# charger.net
KiCad netlist of a schematic drawn in EAGLE
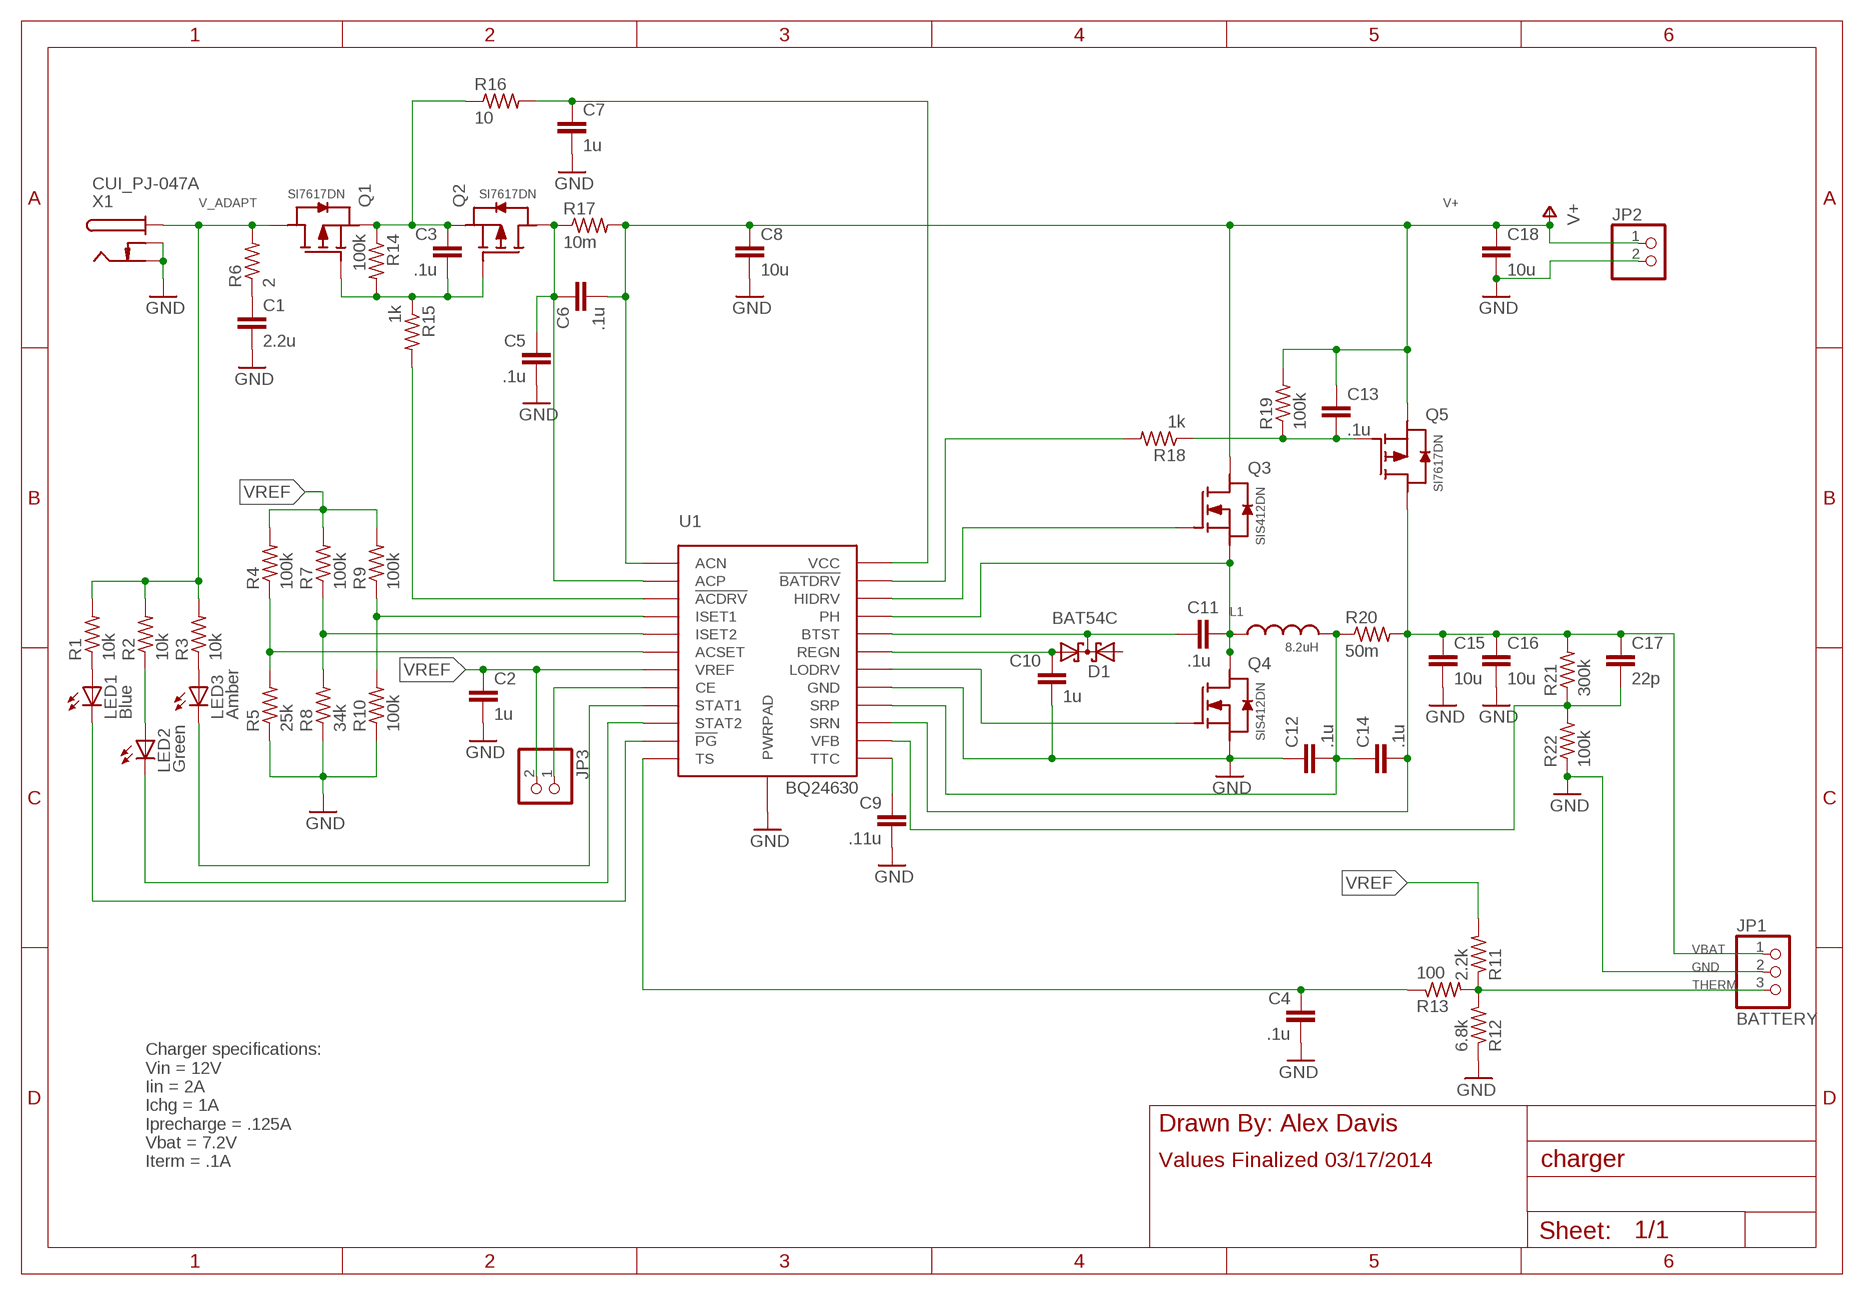
[diagram p0: schematic, sheet 1]

(export (version "E")
  (design (tool "Eeschema 10.0.6"))
  (components
    (comp (ref "C1")
      (value "2.2u")
      (footprint "eagle-import:C0603")
      (libsource (lib "eagle-import") (part "C-EUC0603"))
    )
    (comp (ref "C2")
      (value "1u")
      (footprint "eagle-import:C0603")
      (libsource (lib "eagle-import") (part "C-EUC0603"))
    )
    (comp (ref "C3")
      (value ".1u")
      (footprint "eagle-import:C0603")
      (libsource (lib "eagle-import") (part "C-EUC0603"))
    )
    (comp (ref "C4")
      (value ".1u")
      (footprint "eagle-import:C0603")
      (libsource (lib "eagle-import") (part "C-EUC0603"))
    )
    (comp (ref "C5")
      (value ".1u")
      (footprint "eagle-import:C0603")
      (libsource (lib "eagle-import") (part "C-EUC0603"))
    )
    (comp (ref "C6")
      (value ".1u")
      (footprint "eagle-import:C0603")
      (libsource (lib "eagle-import") (part "C-EUC0603"))
    )
    (comp (ref "C7")
      (value "1u")
      (footprint "eagle-import:C0603")
      (libsource (lib "eagle-import") (part "C-EUC0603"))
    )
    (comp (ref "C8")
      (value "10u")
      (footprint "eagle-import:C0805")
      (libsource (lib "eagle-import") (part "C-EUC0805"))
    )
    (comp (ref "C9")
      (value ".11u")
      (footprint "eagle-import:C0603")
      (libsource (lib "eagle-import") (part "C-EUC0603"))
    )
    (comp (ref "C10")
      (value "1u")
      (footprint "eagle-import:C0603")
      (libsource (lib "eagle-import") (part "C-EUC0603"))
    )
    (comp (ref "C11")
      (value ".1u")
      (footprint "eagle-import:C0603")
      (libsource (lib "eagle-import") (part "C-EUC0603"))
    )
    (comp (ref "C12")
      (value ".1u")
      (footprint "eagle-import:C0603")
      (libsource (lib "eagle-import") (part "C-EUC0603"))
    )
    (comp (ref "C13")
      (value ".1u")
      (footprint "eagle-import:C0603")
      (libsource (lib "eagle-import") (part "C-EUC0603"))
    )
    (comp (ref "C14")
      (value ".1u")
      (footprint "eagle-import:C0603")
      (libsource (lib "eagle-import") (part "C-EUC0603"))
    )
    (comp (ref "C15")
      (value "10u")
      (footprint "eagle-import:C0805")
      (libsource (lib "eagle-import") (part "C-EUC0805"))
    )
    (comp (ref "C16")
      (value "10u")
      (footprint "eagle-import:C0805")
      (libsource (lib "eagle-import") (part "C-EUC0805"))
    )
    (comp (ref "C17")
      (value "22p")
      (footprint "eagle-import:C0603")
      (libsource (lib "eagle-import") (part "C-EUC0603"))
    )
    (comp (ref "C18")
      (value "10u")
      (footprint "eagle-import:C0805")
      (libsource (lib "eagle-import") (part "C-EUC0805"))
    )
    (comp (ref "D1")
      (value "BAT54C")
      (footprint "eagle-import:SOT23")
      (libsource (lib "eagle-import") (part "BAT54C"))
    )
    (comp (ref "JP1")
      (value "BATTERY")
      (footprint "eagle-import:1X03")
      (libsource (lib "eagle-import") (part "PINHD-1X3"))
    )
    (comp (ref "JP2")
      (value "PINHD-1X2")
      (footprint "eagle-import:1X02")
      (libsource (lib "eagle-import") (part "PINHD-1X2"))
    )
    (comp (ref "JP3")
      (value "PINHD-1X2")
      (footprint "eagle-import:1X02")
      (libsource (lib "eagle-import") (part "PINHD-1X2"))
    )
    (comp (ref "L1")
      (value "8.2uH")
      (footprint "eagle-import:IHLP-2525CZ")
      (libsource (lib "eagle-import") (part "IHLP-2525CZ-01"))
    )
    (comp (ref "LED1")
      (value "Blue")
      (footprint "eagle-import:CHIPLED_0805")
      (libsource (lib "eagle-import") (part "LEDCHIPLED_0805"))
    )
    (comp (ref "LED2")
      (value "Green")
      (footprint "eagle-import:CHIPLED_0805")
      (libsource (lib "eagle-import") (part "LEDCHIPLED_0805"))
    )
    (comp (ref "LED3")
      (value "Amber")
      (footprint "eagle-import:CHIPLED_0805")
      (libsource (lib "eagle-import") (part "LEDCHIPLED_0805"))
    )
    (comp (ref "Q1")
      (value "SI7617DN")
      (footprint "eagle-import:POWERPAK1212-8")
      (libsource (lib "eagle-import") (part "SI7617DN"))
    )
    (comp (ref "Q2")
      (value "SI7617DN")
      (footprint "eagle-import:POWERPAK1212-8")
      (libsource (lib "eagle-import") (part "SI7617DN"))
    )
    (comp (ref "Q3")
      (value "SIS412DN")
      (footprint "eagle-import:POWERPAK1212-8")
      (libsource (lib "eagle-import") (part "SIS412DN"))
    )
    (comp (ref "Q4")
      (value "SIS412DN")
      (footprint "eagle-import:POWERPAK1212-8")
      (libsource (lib "eagle-import") (part "SIS412DN"))
    )
    (comp (ref "Q5")
      (value "SI7617DN")
      (footprint "eagle-import:POWERPAK1212-8")
      (libsource (lib "eagle-import") (part "SI7617DN"))
    )
    (comp (ref "R1")
      (value "10k")
      (footprint "eagle-import:R0603")
      (libsource (lib "eagle-import") (part "R-US_R0603"))
    )
    (comp (ref "R2")
      (value "10k")
      (footprint "eagle-import:R0603")
      (libsource (lib "eagle-import") (part "R-US_R0603"))
    )
    (comp (ref "R3")
      (value "10k")
      (footprint "eagle-import:R0603")
      (libsource (lib "eagle-import") (part "R-US_R0603"))
    )
    (comp (ref "R4")
      (value "100k")
      (footprint "eagle-import:R0603")
      (libsource (lib "eagle-import") (part "R-US_R0603"))
    )
    (comp (ref "R5")
      (value "25k")
      (footprint "eagle-import:R0603")
      (libsource (lib "eagle-import") (part "R-US_R0603"))
    )
    (comp (ref "R6")
      (value "2")
      (footprint "eagle-import:R2512")
      (libsource (lib "eagle-import") (part "R-US_R2512"))
    )
    (comp (ref "R7")
      (value "100k")
      (footprint "eagle-import:R0603")
      (libsource (lib "eagle-import") (part "R-US_R0603"))
    )
    (comp (ref "R8")
      (value "34k")
      (footprint "eagle-import:R0603")
      (libsource (lib "eagle-import") (part "R-US_R0603"))
    )
    (comp (ref "R9")
      (value "100k")
      (footprint "eagle-import:R0603")
      (libsource (lib "eagle-import") (part "R-US_R0603"))
    )
    (comp (ref "R10")
      (value "100k")
      (footprint "eagle-import:R0603")
      (libsource (lib "eagle-import") (part "R-US_R0603"))
    )
    (comp (ref "R11")
      (value "2.2k")
      (footprint "eagle-import:R0603")
      (libsource (lib "eagle-import") (part "R-US_R0603"))
    )
    (comp (ref "R12")
      (value "6.8k")
      (footprint "eagle-import:R0603")
      (libsource (lib "eagle-import") (part "R-US_R0603"))
    )
    (comp (ref "R13")
      (value "100")
      (footprint "eagle-import:R0603")
      (libsource (lib "eagle-import") (part "R-US_R0603"))
    )
    (comp (ref "R14")
      (value "100k")
      (footprint "eagle-import:R0603")
      (libsource (lib "eagle-import") (part "R-US_R0603"))
    )
    (comp (ref "R15")
      (value "1k")
      (footprint "eagle-import:R0603")
      (libsource (lib "eagle-import") (part "R-US_R0603"))
    )
    (comp (ref "R16")
      (value "10")
      (footprint "eagle-import:R1206")
      (libsource (lib "eagle-import") (part "R-US_R1206"))
    )
    (comp (ref "R17")
      (value "10m")
      (footprint "eagle-import:R2010")
      (libsource (lib "eagle-import") (part "R-US_R2010"))
    )
    (comp (ref "R18")
      (value "1k")
      (footprint "eagle-import:R0603")
      (libsource (lib "eagle-import") (part "R-US_R0603"))
    )
    (comp (ref "R19")
      (value "100k")
      (footprint "eagle-import:R0603")
      (libsource (lib "eagle-import") (part "R-US_R0603"))
    )
    (comp (ref "R20")
      (value "50m")
      (footprint "eagle-import:R2010")
      (libsource (lib "eagle-import") (part "R-US_R2010"))
    )
    (comp (ref "R21")
      (value "300k")
      (footprint "eagle-import:R0603")
      (libsource (lib "eagle-import") (part "R-US_R0603"))
    )
    (comp (ref "R22")
      (value "100k")
      (footprint "eagle-import:R0603")
      (libsource (lib "eagle-import") (part "R-US_R0603"))
    )
    (comp (ref "U1")
      (value "BQ24630")
      (footprint "eagle-import:PVQFN-24")
      (libsource (lib "eagle-import") (part "BQ24630"))
    )
    (comp (ref "X1")
      (value "CUI_PJ-047A")
      (footprint "eagle-import:PJ-047A")
      (libsource (lib "eagle-import") (part "CON-PWR"))
    )
  )
  (nets
    (net (code "1") (name "/THERM") (class "Default")
      (node (ref "JP1") (pin "3") (pinfunction "3_3") (pintype "passive"))
      (node (ref "R11") (pin "1") (pinfunction "1_1") (pintype "passive"))
      (node (ref "R12") (pin "2") (pinfunction "2_2") (pintype "passive"))
      (node (ref "R13") (pin "2") (pinfunction "2_2") (pintype "passive"))
    )
    (net (code "2") (name "/VBAT") (class "Default")
      (node (ref "C14") (pin "2") (pinfunction "2_2") (pintype "passive"))
      (node (ref "C15") (pin "1") (pinfunction "1_1") (pintype "passive"))
      (node (ref "C16") (pin "1") (pinfunction "1_1") (pintype "passive"))
      (node (ref "C17") (pin "1") (pinfunction "1_1") (pintype "passive"))
      (node (ref "JP1") (pin "1") (pinfunction "1_1") (pintype "passive"))
      (node (ref "Q5") (pin "P$5") (pinfunction "D_P$5") (pintype "bidirectional"))
      (node (ref "Q5") (pin "P$6") (pinfunction "D_P$6") (pintype "bidirectional"))
      (node (ref "Q5") (pin "P$7") (pinfunction "D_P$7") (pintype "bidirectional"))
      (node (ref "Q5") (pin "P$8") (pinfunction "D_P$8") (pintype "bidirectional"))
      (node (ref "Q5") (pin "P$9") (pinfunction "D_P$9") (pintype "bidirectional"))
      (node (ref "R20") (pin "2") (pinfunction "2_2") (pintype "passive"))
      (node (ref "R21") (pin "2") (pinfunction "2_2") (pintype "passive"))
      (node (ref "U1") (pin "P$13") (pinfunction "SRN_P$13") (pintype "bidirectional"))
    )
    (net (code "3") (name "/V_ADAPT") (class "Default")
      (node (ref "Q1") (pin "P$5") (pinfunction "D_P$5") (pintype "bidirectional"))
      (node (ref "Q1") (pin "P$6") (pinfunction "D_P$6") (pintype "bidirectional"))
      (node (ref "Q1") (pin "P$7") (pinfunction "D_P$7") (pintype "bidirectional"))
      (node (ref "Q1") (pin "P$8") (pinfunction "D_P$8") (pintype "bidirectional"))
      (node (ref "Q1") (pin "P$9") (pinfunction "D_P$9") (pintype "bidirectional"))
      (node (ref "R1") (pin "2") (pinfunction "2_2") (pintype "passive"))
      (node (ref "R2") (pin "2") (pinfunction "2_2") (pintype "passive"))
      (node (ref "R3") (pin "2") (pinfunction "2_2") (pintype "passive"))
      (node (ref "R6") (pin "2") (pinfunction "2_2") (pintype "passive"))
      (node (ref "X1") (pin "1") (pinfunction "1_1") (pintype "bidirectional"))
    )
    (net (code "4") (name "GND") (class "Default")
      (node (ref "C1") (pin "2") (pinfunction "2_2") (pintype "passive"))
      (node (ref "C10") (pin "2") (pinfunction "2_2") (pintype "passive"))
      (node (ref "C12") (pin "1") (pinfunction "1_1") (pintype "passive"))
      (node (ref "C15") (pin "2") (pinfunction "2_2") (pintype "passive"))
      (node (ref "C16") (pin "2") (pinfunction "2_2") (pintype "passive"))
      (node (ref "C18") (pin "2") (pinfunction "2_2") (pintype "passive"))
      (node (ref "C2") (pin "2") (pinfunction "2_2") (pintype "passive"))
      (node (ref "C4") (pin "2") (pinfunction "2_2") (pintype "passive"))
      (node (ref "C5") (pin "2") (pinfunction "2_2") (pintype "passive"))
      (node (ref "C7") (pin "2") (pinfunction "2_2") (pintype "passive"))
      (node (ref "C8") (pin "2") (pinfunction "2_2") (pintype "passive"))
      (node (ref "C9") (pin "2") (pinfunction "2_2") (pintype "passive"))
      (node (ref "JP1") (pin "2") (pinfunction "2_2") (pintype "passive"))
      (node (ref "JP2") (pin "2") (pinfunction "2_2") (pintype "passive"))
      (node (ref "Q4") (pin "P$1") (pinfunction "S_P$1") (pintype "bidirectional"))
      (node (ref "Q4") (pin "P$2") (pinfunction "S_P$2") (pintype "bidirectional"))
      (node (ref "Q4") (pin "P$3") (pinfunction "S_P$3") (pintype "bidirectional"))
      (node (ref "R10") (pin "1") (pinfunction "1_1") (pintype "passive"))
      (node (ref "R12") (pin "1") (pinfunction "1_1") (pintype "passive"))
      (node (ref "R22") (pin "1") (pinfunction "1_1") (pintype "passive"))
      (node (ref "R5") (pin "1") (pinfunction "1_1") (pintype "passive"))
      (node (ref "R8") (pin "1") (pinfunction "1_1") (pintype "passive"))
      (node (ref "U1") (pin "P$17") (pinfunction "GND_P$17") (pintype "bidirectional"))
      (node (ref "U1") (pin "P$25") (pinfunction "PWRPAD_P$25") (pintype "bidirectional"))
      (node (ref "X1") (pin "2") (pinfunction "2_2") (pintype "bidirectional"))
      (node (ref "X1") (pin "3") (pinfunction "3_3") (pintype "bidirectional"))
    )
    (net (code "5") (name "Net-(C1-Pad1)") (class "Default")
      (node (ref "C1") (pin "1") (pinfunction "1_1") (pintype "passive"))
      (node (ref "R6") (pin "1") (pinfunction "1_1") (pintype "passive"))
    )
    (net (code "6") (name "Net-(C3-Pad1)") (class "Default")
      (node (ref "C3") (pin "1") (pinfunction "1_1") (pintype "passive"))
      (node (ref "Q1") (pin "P$1") (pinfunction "S_P$1") (pintype "bidirectional"))
      (node (ref "Q1") (pin "P$2") (pinfunction "S_P$2") (pintype "bidirectional"))
      (node (ref "Q1") (pin "P$3") (pinfunction "S_P$3") (pintype "bidirectional"))
      (node (ref "Q2") (pin "P$1") (pinfunction "S_P$1") (pintype "bidirectional"))
      (node (ref "Q2") (pin "P$2") (pinfunction "S_P$2") (pintype "bidirectional"))
      (node (ref "Q2") (pin "P$3") (pinfunction "S_P$3") (pintype "bidirectional"))
      (node (ref "R14") (pin "1") (pinfunction "1_1") (pintype "passive"))
      (node (ref "R16") (pin "1") (pinfunction "1_1") (pintype "passive"))
    )
    (net (code "7") (name "Net-(D1-A2)") (class "Default")
      (node (ref "C10") (pin "1") (pinfunction "1_1") (pintype "passive"))
      (node (ref "D1") (pin "2") (pinfunction "A2_2") (pintype "passive"))
      (node (ref "U1") (pin "P$18") (pinfunction "REGN_P$18") (pintype "bidirectional"))
    )
    (net (code "8") (name "Net-(D1-CC)") (class "Default")
      (node (ref "C11") (pin "1") (pinfunction "1_1") (pintype "passive"))
      (node (ref "D1") (pin "3") (pinfunction "CC_3") (pintype "passive"))
      (node (ref "U1") (pin "P$22") (pinfunction "BTST_P$22") (pintype "bidirectional"))
    )
    (net (code "9") (name "Net-(LED1-PadA)") (class "Default")
      (node (ref "LED1") (pin "A") (pinfunction "A_A") (pintype "passive"))
      (node (ref "R1") (pin "1") (pinfunction "1_1") (pintype "passive"))
    )
    (net (code "10") (name "Net-(LED2-PadA)") (class "Default")
      (node (ref "LED2") (pin "A") (pinfunction "A_A") (pintype "passive"))
      (node (ref "R2") (pin "1") (pinfunction "1_1") (pintype "passive"))
    )
    (net (code "11") (name "Net-(LED3-PadA)") (class "Default")
      (node (ref "LED3") (pin "A") (pinfunction "A_A") (pintype "passive"))
      (node (ref "R3") (pin "1") (pinfunction "1_1") (pintype "passive"))
    )
    (net (code "12") (name "Net-(Q1-G)") (class "Default")
      (node (ref "C3") (pin "2") (pinfunction "2_2") (pintype "passive"))
      (node (ref "Q1") (pin "P$4") (pinfunction "G_P$4") (pintype "bidirectional"))
      (node (ref "Q2") (pin "P$4") (pinfunction "G_P$4") (pintype "bidirectional"))
      (node (ref "R14") (pin "2") (pinfunction "2_2") (pintype "passive"))
      (node (ref "R15") (pin "1") (pinfunction "1_1") (pintype "passive"))
    )
    (net (code "13") (name "Net-(Q3-G)") (class "Default")
      (node (ref "Q3") (pin "P$4") (pinfunction "G_P$4") (pintype "bidirectional"))
      (node (ref "U1") (pin "P$21") (pinfunction "HIDRV_P$21") (pintype "bidirectional"))
    )
    (net (code "14") (name "Net-(Q4-G)") (class "Default")
      (node (ref "Q4") (pin "P$4") (pinfunction "G_P$4") (pintype "bidirectional"))
      (node (ref "U1") (pin "P$19") (pinfunction "LODRV_P$19") (pintype "bidirectional"))
    )
    (net (code "15") (name "Net-(Q5-G)") (class "Default")
      (node (ref "C13") (pin "2") (pinfunction "2_2") (pintype "passive"))
      (node (ref "Q5") (pin "P$4") (pinfunction "G_P$4") (pintype "bidirectional"))
      (node (ref "R18") (pin "1") (pinfunction "1_1") (pintype "passive"))
      (node (ref "R19") (pin "1") (pinfunction "1_1") (pintype "passive"))
    )
    (net (code "16") (name "Net-(U1-ACP)") (class "Default")
      (node (ref "C5") (pin "1") (pinfunction "1_1") (pintype "passive"))
      (node (ref "C6") (pin "1") (pinfunction "1_1") (pintype "passive"))
      (node (ref "Q2") (pin "P$5") (pinfunction "D_P$5") (pintype "bidirectional"))
      (node (ref "Q2") (pin "P$6") (pinfunction "D_P$6") (pintype "bidirectional"))
      (node (ref "Q2") (pin "P$7") (pinfunction "D_P$7") (pintype "bidirectional"))
      (node (ref "Q2") (pin "P$8") (pinfunction "D_P$8") (pintype "bidirectional"))
      (node (ref "Q2") (pin "P$9") (pinfunction "D_P$9") (pintype "bidirectional"))
      (node (ref "R17") (pin "1") (pinfunction "1_1") (pintype "passive"))
      (node (ref "U1") (pin "P$2") (pinfunction "ACP_P$2") (pintype "bidirectional"))
    )
    (net (code "17") (name "Net-(U1-ACSET)") (class "Default")
      (node (ref "R4") (pin "1") (pinfunction "1_1") (pintype "passive"))
      (node (ref "R5") (pin "2") (pinfunction "2_2") (pintype "passive"))
      (node (ref "U1") (pin "P$16") (pinfunction "ACSET_P$16") (pintype "bidirectional"))
    )
    (net (code "18") (name "Net-(U1-CE)") (class "Default")
      (node (ref "JP3") (pin "1") (pinfunction "1_1") (pintype "passive"))
      (node (ref "U1") (pin "P$4") (pinfunction "CE_P$4") (pintype "bidirectional"))
    )
    (net (code "19") (name "Net-(U1-ISET1)") (class "Default")
      (node (ref "R10") (pin "2") (pinfunction "2_2") (pintype "passive"))
      (node (ref "R9") (pin "1") (pinfunction "1_1") (pintype "passive"))
      (node (ref "U1") (pin "P$11") (pinfunction "ISET1_P$11") (pintype "bidirectional"))
    )
    (net (code "20") (name "Net-(U1-ISET2)") (class "Default")
      (node (ref "R7") (pin "1") (pinfunction "1_1") (pintype "passive"))
      (node (ref "R8") (pin "2") (pinfunction "2_2") (pintype "passive"))
      (node (ref "U1") (pin "P$15") (pinfunction "ISET2_P$15") (pintype "bidirectional"))
    )
    (net (code "21") (name "Net-(U1-PH)") (class "Default")
      (node (ref "C11") (pin "2") (pinfunction "2_2") (pintype "passive"))
      (node (ref "L1") (pin "P$1") (pinfunction "P$1_P$1") (pintype "bidirectional"))
      (node (ref "Q3") (pin "P$1") (pinfunction "S_P$1") (pintype "bidirectional"))
      (node (ref "Q3") (pin "P$2") (pinfunction "S_P$2") (pintype "bidirectional"))
      (node (ref "Q3") (pin "P$3") (pinfunction "S_P$3") (pintype "bidirectional"))
      (node (ref "Q4") (pin "P$5") (pinfunction "D_P$5") (pintype "bidirectional"))
      (node (ref "Q4") (pin "P$6") (pinfunction "D_P$6") (pintype "bidirectional"))
      (node (ref "Q4") (pin "P$7") (pinfunction "D_P$7") (pintype "bidirectional"))
      (node (ref "Q4") (pin "P$8") (pinfunction "D_P$8") (pintype "bidirectional"))
      (node (ref "Q4") (pin "P$9") (pinfunction "D_P$9") (pintype "bidirectional"))
      (node (ref "U1") (pin "P$20") (pinfunction "PH_P$20") (pintype "bidirectional"))
    )
    (net (code "22") (name "Net-(U1-SRP)") (class "Default")
      (node (ref "C12") (pin "2") (pinfunction "2_2") (pintype "passive"))
      (node (ref "C14") (pin "1") (pinfunction "1_1") (pintype "passive"))
      (node (ref "L1") (pin "P$2") (pinfunction "P$2_P$2") (pintype "bidirectional"))
      (node (ref "R20") (pin "1") (pinfunction "1_1") (pintype "passive"))
      (node (ref "U1") (pin "P$14") (pinfunction "SRP_P$14") (pintype "bidirectional"))
    )
    (net (code "23") (name "Net-(U1-STAT1)") (class "Default")
      (node (ref "LED3") (pin "C") (pinfunction "C_C") (pintype "passive"))
      (node (ref "U1") (pin "P$5") (pinfunction "STAT1_P$5") (pintype "bidirectional"))
    )
    (net (code "24") (name "Net-(U1-STAT2)") (class "Default")
      (node (ref "LED2") (pin "C") (pinfunction "C_C") (pintype "passive"))
      (node (ref "U1") (pin "P$9") (pinfunction "STAT2_P$9") (pintype "bidirectional"))
    )
    (net (code "25") (name "Net-(U1-TS)") (class "Default")
      (node (ref "C4") (pin "1") (pinfunction "1_1") (pintype "passive"))
      (node (ref "R13") (pin "1") (pinfunction "1_1") (pintype "passive"))
      (node (ref "U1") (pin "P$6") (pinfunction "TS_P$6") (pintype "bidirectional"))
    )
    (net (code "26") (name "Net-(U1-TTC)") (class "Default")
      (node (ref "C9") (pin "1") (pinfunction "1_1") (pintype "passive"))
      (node (ref "U1") (pin "P$7") (pinfunction "TTC_P$7") (pintype "bidirectional"))
    )
    (net (code "27") (name "Net-(U1-VCC)") (class "Default")
      (node (ref "C7") (pin "1") (pinfunction "1_1") (pintype "passive"))
      (node (ref "R16") (pin "2") (pinfunction "2_2") (pintype "passive"))
      (node (ref "U1") (pin "P$24") (pinfunction "VCC_P$24") (pintype "bidirectional"))
    )
    (net (code "28") (name "Net-(U1-VFB)") (class "Default")
      (node (ref "C17") (pin "2") (pinfunction "2_2") (pintype "passive"))
      (node (ref "R21") (pin "1") (pinfunction "1_1") (pintype "passive"))
      (node (ref "R22") (pin "2") (pinfunction "2_2") (pintype "passive"))
      (node (ref "U1") (pin "P$12") (pinfunction "VFB_P$12") (pintype "bidirectional"))
    )
    (net (code "29") (name "Net-(U1-~{ACDRV})") (class "Default")
      (node (ref "R15") (pin "2") (pinfunction "2_2") (pintype "passive"))
      (node (ref "U1") (pin "P$3") (pinfunction "~{ACDRV}_P$3") (pintype "bidirectional"))
    )
    (net (code "30") (name "Net-(U1-~{BATDRV})") (class "Default")
      (node (ref "R18") (pin "2") (pinfunction "2_2") (pintype "passive"))
      (node (ref "U1") (pin "P$23") (pinfunction "~{BATDRV}_P$23") (pintype "bidirectional"))
    )
    (net (code "31") (name "Net-(U1-~{PG})") (class "Default")
      (node (ref "LED1") (pin "C") (pinfunction "C_C") (pintype "passive"))
      (node (ref "U1") (pin "P$8") (pinfunction "~{PG}_P$8") (pintype "bidirectional"))
    )
    (net (code "32") (name "V+") (class "Default")
      (node (ref "C13") (pin "1") (pinfunction "1_1") (pintype "passive"))
      (node (ref "C18") (pin "1") (pinfunction "1_1") (pintype "passive"))
      (node (ref "C6") (pin "2") (pinfunction "2_2") (pintype "passive"))
      (node (ref "C8") (pin "1") (pinfunction "1_1") (pintype "passive"))
      (node (ref "JP2") (pin "1") (pinfunction "1_1") (pintype "passive"))
      (node (ref "Q3") (pin "P$5") (pinfunction "D_P$5") (pintype "bidirectional"))
      (node (ref "Q3") (pin "P$6") (pinfunction "D_P$6") (pintype "bidirectional"))
      (node (ref "Q3") (pin "P$7") (pinfunction "D_P$7") (pintype "bidirectional"))
      (node (ref "Q3") (pin "P$8") (pinfunction "D_P$8") (pintype "bidirectional"))
      (node (ref "Q3") (pin "P$9") (pinfunction "D_P$9") (pintype "bidirectional"))
      (node (ref "Q5") (pin "P$1") (pinfunction "S_P$1") (pintype "bidirectional"))
      (node (ref "Q5") (pin "P$2") (pinfunction "S_P$2") (pintype "bidirectional"))
      (node (ref "Q5") (pin "P$3") (pinfunction "S_P$3") (pintype "bidirectional"))
      (node (ref "R17") (pin "2") (pinfunction "2_2") (pintype "passive"))
      (node (ref "R19") (pin "2") (pinfunction "2_2") (pintype "passive"))
      (node (ref "U1") (pin "P$1") (pinfunction "ACN_P$1") (pintype "bidirectional"))
    )
    (net (code "33") (name "VREF") (class "Default")
      (node (ref "C2") (pin "1") (pinfunction "1_1") (pintype "passive"))
      (node (ref "JP3") (pin "2") (pinfunction "2_2") (pintype "passive"))
      (node (ref "R11") (pin "2") (pinfunction "2_2") (pintype "passive"))
      (node (ref "R4") (pin "2") (pinfunction "2_2") (pintype "passive"))
      (node (ref "R7") (pin "2") (pinfunction "2_2") (pintype "passive"))
      (node (ref "R9") (pin "2") (pinfunction "2_2") (pintype "passive"))
      (node (ref "U1") (pin "P$10") (pinfunction "VREF_P$10") (pintype "bidirectional"))
    )
    (net (code "34") (name "unconnected-(D1-A1-Pad1)") (class "Default")
      (node (ref "D1") (pin "1") (pinfunction "A1_1") (pintype "passive"))
    )
  )
)
